# A-fex_PowerShell.net
KiCad netlist of a schematic drawn in EasyEDA Pro
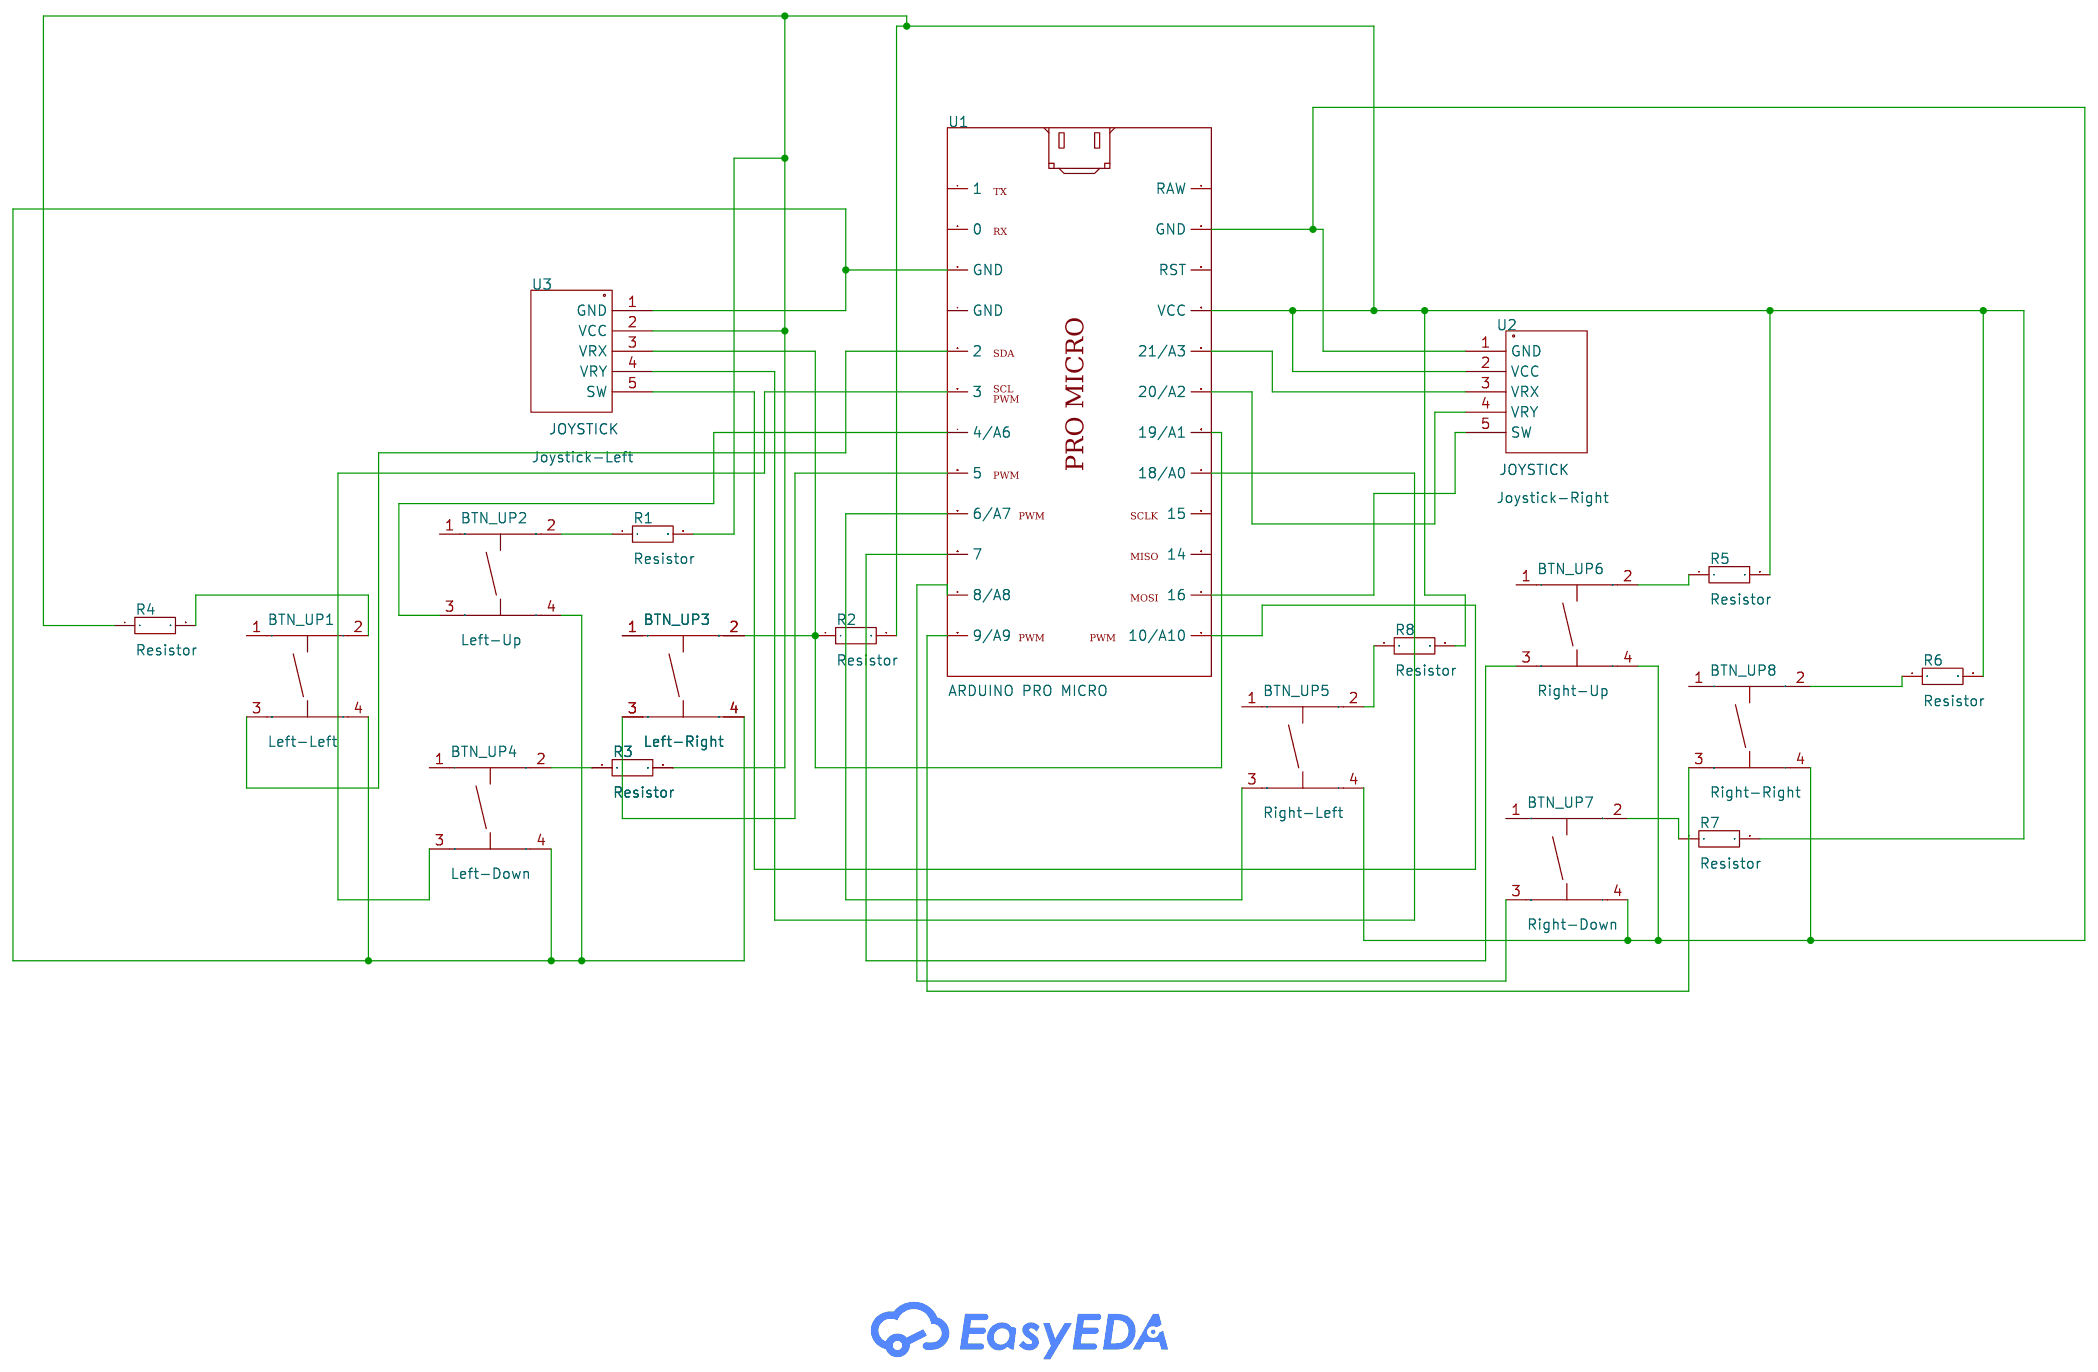
[diagram p0: schematic sheet]

(export (version "E")
  (design (tool "Eeschema 10.0.6"))
  (components
    (comp (ref "BTN_UP1")
      (value "Left-Left")
      (footprint "easyedapro:SW-TH_4P-L12.0-W12.0-P5.00-LS12.5")
      (fields (field (name "Manufacturer") "Boom Precision Elec"))
      (libsource (lib "easyedapro") (part "12X12X7.3 PLAIN TACTILE PUSHBUTTON"))
    )
    (comp (ref "BTN_UP2")
      (value "Left-Up")
      (footprint "easyedapro:SW-TH_4P-L12.0-W12.0-P5.00-LS12.5")
      (fields (field (name "Manufacturer") "Boom Precision Elec"))
      (libsource (lib "easyedapro") (part "12X12X7.3 PLAIN TACTILE PUSHBUTTON"))
    )
    (comp (ref "BTN_UP3")
      (value "Left-Right")
      (footprint "easyedapro:SW-TH_4P-L12.0-W12.0-P5.00-LS12.5")
      (fields (field (name "Manufacturer") "Boom Precision Elec"))
      (libsource (lib "easyedapro") (part "12X12X7.3 PLAIN TACTILE PUSHBUTTON"))
    )
    (comp (ref "BTN_UP4")
      (value "Left-Down")
      (footprint "easyedapro:SW-TH_4P-L12.0-W12.0-P5.00-LS12.5")
      (fields (field (name "Manufacturer") "Boom Precision Elec"))
      (libsource (lib "easyedapro") (part "12X12X7.3 PLAIN TACTILE PUSHBUTTON"))
    )
    (comp (ref "BTN_UP5")
      (value "Right-Left")
      (footprint "easyedapro:SW-TH_4P-L12.0-W12.0-P5.00-LS12.5")
      (fields (field (name "Manufacturer") "Boom Precision Elec"))
      (libsource (lib "easyedapro") (part "12X12X7.3 PLAIN TACTILE PUSHBUTTON"))
    )
    (comp (ref "BTN_UP6")
      (value "Right-Up")
      (footprint "easyedapro:SW-TH_4P-L12.0-W12.0-P5.00-LS12.5")
      (fields (field (name "Manufacturer") "Boom Precision Elec"))
      (libsource (lib "easyedapro") (part "12X12X7.3 PLAIN TACTILE PUSHBUTTON"))
    )
    (comp (ref "BTN_UP7")
      (value "Right-Down")
      (footprint "easyedapro:SW-TH_4P-L12.0-W12.0-P5.00-LS12.5")
      (fields (field (name "Manufacturer") "Boom Precision Elec"))
      (libsource (lib "easyedapro") (part "12X12X7.3 PLAIN TACTILE PUSHBUTTON"))
    )
    (comp (ref "BTN_UP8")
      (value "Right-Right")
      (footprint "easyedapro:SW-TH_4P-L12.0-W12.0-P5.00-LS12.5")
      (fields (field (name "Manufacturer") "Boom Precision Elec"))
      (libsource (lib "easyedapro") (part "12X12X7.3 PLAIN TACTILE PUSHBUTTON"))
    )
    (comp (ref "R1")
      (value "Resistor")
      (footprint "easyedapro:Resistor 1/8w 7mm metal film")
      (fields
        (field (name "Manufacturer Part") "1206W4F1002T5E")
        (field (name "Manufacturer") "UNI-ROYAL(Uniroyal Elec)")
      )
      (libsource (lib "easyedapro") (part "resistor"))
    )
    (comp (ref "R2")
      (value "Resistor")
      (footprint "easyedapro:Resistor 1/8w 7mm metal film")
      (fields
        (field (name "Manufacturer Part") "1206W4F1002T5E")
        (field (name "Manufacturer") "UNI-ROYAL(Uniroyal Elec)")
      )
      (libsource (lib "easyedapro") (part "resistor"))
    )
    (comp (ref "R3")
      (value "Resistor")
      (footprint "easyedapro:Resistor 1/8w 7mm metal film")
      (fields
        (field (name "Manufacturer Part") "1206W4F1002T5E")
        (field (name "Manufacturer") "UNI-ROYAL(Uniroyal Elec)")
      )
      (libsource (lib "easyedapro") (part "resistor"))
    )
    (comp (ref "R4")
      (value "Resistor")
      (footprint "easyedapro:Resistor 1/8w 7mm metal film")
      (fields
        (field (name "Manufacturer Part") "1206W4F1002T5E")
        (field (name "Manufacturer") "UNI-ROYAL(Uniroyal Elec)")
      )
      (libsource (lib "easyedapro") (part "resistor"))
    )
    (comp (ref "R5")
      (value "Resistor")
      (footprint "easyedapro:Resistor 1/8w 7mm metal film")
      (fields
        (field (name "Manufacturer Part") "1206W4F1002T5E")
        (field (name "Manufacturer") "UNI-ROYAL(Uniroyal Elec)")
      )
      (libsource (lib "easyedapro") (part "resistor"))
    )
    (comp (ref "R6")
      (value "Resistor")
      (footprint "easyedapro:Resistor 1/8w 7mm metal film")
      (fields
        (field (name "Manufacturer Part") "1206W4F1002T5E")
        (field (name "Manufacturer") "UNI-ROYAL(Uniroyal Elec)")
      )
      (libsource (lib "easyedapro") (part "resistor"))
    )
    (comp (ref "R7")
      (value "Resistor")
      (footprint "easyedapro:Resistor 1/8w 7mm metal film")
      (fields
        (field (name "Manufacturer Part") "1206W4F1002T5E")
        (field (name "Manufacturer") "UNI-ROYAL(Uniroyal Elec)")
      )
      (libsource (lib "easyedapro") (part "resistor"))
    )
    (comp (ref "R8")
      (value "Resistor")
      (footprint "easyedapro:Resistor 1/8w 7mm metal film")
      (fields
        (field (name "Manufacturer Part") "1206W4F1002T5E")
        (field (name "Manufacturer") "UNI-ROYAL(Uniroyal Elec)")
      )
      (libsource (lib "easyedapro") (part "resistor"))
    )
    (comp (ref "U1")
      (value "ARDUINO PRO MICRO")
      (footprint "easyedapro:ARDUINO MICRO PRO")
      (description "Arduino Pro Micro ATMEGA32U4")
      (fields (field (name "Manufacturer Part") "Arduino Micro Pro"))
      (libsource (lib "easyedapro") (part "ARDUINO PRO MICRO"))
    )
    (comp (ref "U2")
      (value "Joystick-Right")
      (footprint "easyedapro:JOYSTICK")
      (libsource (lib "easyedapro") (part "JOYSTICK"))
    )
    (comp (ref "U3")
      (value "Joystick-Left")
      (footprint "easyedapro:JOYSTICK")
      (libsource (lib "easyedapro") (part "JOYSTICK"))
    )
  )
  (nets
    (net (code "1") (name "Net-(BTN_UP1-Pad2)") (class "Default")
      (node (ref "BTN_UP1") (pin "2") (pinfunction "2_2") (pintype "unspecified"))
      (node (ref "R4") (pin "2") (pinfunction "2_2") (pintype "input"))
    )
    (net (code "2") (name "Net-(BTN_UP2-Pad2)") (class "Default")
      (node (ref "BTN_UP2") (pin "2") (pinfunction "2_2") (pintype "unspecified"))
      (node (ref "R1") (pin "1") (pinfunction "1_1") (pintype "input"))
    )
    (net (code "3") (name "Net-(BTN_UP4-Pad2)") (class "Default")
      (node (ref "BTN_UP4") (pin "2") (pinfunction "2_2") (pintype "unspecified"))
      (node (ref "R3") (pin "1") (pinfunction "1_1") (pintype "input"))
    )
    (net (code "4") (name "Net-(BTN_UP5-Pad2)") (class "Default")
      (node (ref "BTN_UP5") (pin "2") (pinfunction "2_2") (pintype "unspecified"))
      (node (ref "R8") (pin "1") (pinfunction "1_1") (pintype "input"))
    )
    (net (code "5") (name "Net-(BTN_UP6-Pad2)") (class "Default")
      (node (ref "BTN_UP6") (pin "2") (pinfunction "2_2") (pintype "unspecified"))
      (node (ref "R5") (pin "1") (pinfunction "1_1") (pintype "input"))
    )
    (net (code "6") (name "Net-(BTN_UP7-Pad2)") (class "Default")
      (node (ref "BTN_UP7") (pin "2") (pinfunction "2_2") (pintype "unspecified"))
      (node (ref "R7") (pin "1") (pinfunction "1_1") (pintype "input"))
    )
    (net (code "7") (name "Net-(BTN_UP8-Pad2)") (class "Default")
      (node (ref "BTN_UP8") (pin "2") (pinfunction "2_2") (pintype "unspecified"))
      (node (ref "R6") (pin "1") (pinfunction "1_1") (pintype "input"))
    )
    (net (code "8") (name "Net-(U1-2)") (class "Default")
      (node (ref "BTN_UP1") (pin "3") (pinfunction "3_3") (pintype "unspecified"))
      (node (ref "U1") (pin "5") (pinfunction "2_5") (pintype "input"))
    )
    (net (code "9") (name "Net-(U1-3)") (class "Default")
      (node (ref "BTN_UP4") (pin "3") (pinfunction "3_3") (pintype "unspecified"))
      (node (ref "U1") (pin "6") (pinfunction "3_6") (pintype "input"))
    )
    (net (code "10") (name "Net-(U1-4{slash}A6)") (class "Default")
      (node (ref "BTN_UP2") (pin "3") (pinfunction "3_3") (pintype "unspecified"))
      (node (ref "U1") (pin "7") (pinfunction "4/A6_7") (pintype "input"))
    )
    (net (code "11") (name "Net-(U1-5)") (class "Default")
      (node (ref "BTN_UP3") (pin "3") (pinfunction "3_3") (pintype "unspecified"))
      (node (ref "U1") (pin "8") (pinfunction "5_8") (pintype "input"))
    )
    (net (code "12") (name "Net-(U1-6{slash}A7)") (class "Default")
      (node (ref "BTN_UP5") (pin "3") (pinfunction "3_3") (pintype "unspecified"))
      (node (ref "U1") (pin "9") (pinfunction "6/A7_9") (pintype "input"))
    )
    (net (code "13") (name "Net-(U1-7)") (class "Default")
      (node (ref "BTN_UP6") (pin "3") (pinfunction "3_3") (pintype "unspecified"))
      (node (ref "U1") (pin "10") (pinfunction "7_10") (pintype "input"))
    )
    (net (code "14") (name "Net-(U1-8{slash}A8)") (class "Default")
      (node (ref "BTN_UP7") (pin "3") (pinfunction "3_3") (pintype "unspecified"))
      (node (ref "U1") (pin "11") (pinfunction "8/A8_11") (pintype "input"))
    )
    (net (code "15") (name "Net-(U1-9{slash}A9)") (class "Default")
      (node (ref "BTN_UP8") (pin "3") (pinfunction "3_3") (pintype "unspecified"))
      (node (ref "U1") (pin "12") (pinfunction "9/A9_12") (pintype "input"))
    )
    (net (code "16") (name "Net-(U1-10{slash}A10)") (class "Default")
      (node (ref "U1") (pin "13") (pinfunction "10/A10_13") (pintype "input"))
      (node (ref "U3") (pin "5") (pinfunction "SW_5") (pintype "input"))
    )
    (net (code "17") (name "Net-(U1-16)") (class "Default")
      (node (ref "U1") (pin "14") (pinfunction "16_14") (pintype "input"))
      (node (ref "U2") (pin "5") (pinfunction "SW_5") (pintype "input"))
    )
    (net (code "18") (name "Net-(U1-18{slash}A0)") (class "Default")
      (node (ref "U1") (pin "17") (pinfunction "18/A0_17") (pintype "input"))
      (node (ref "U3") (pin "4") (pinfunction "VRY_4") (pintype "input"))
    )
    (net (code "19") (name "Net-(U1-19{slash}A1)") (class "Default")
      (node (ref "BTN_UP3") (pin "2") (pinfunction "2_2") (pintype "unspecified"))
      (node (ref "R2") (pin "1") (pinfunction "1_1") (pintype "input"))
      (node (ref "U1") (pin "18") (pinfunction "19/A1_18") (pintype "input"))
      (node (ref "U3") (pin "3") (pinfunction "VRX_3") (pintype "input"))
    )
    (net (code "20") (name "Net-(U1-20{slash}A2)") (class "Default")
      (node (ref "U1") (pin "19") (pinfunction "20/A2_19") (pintype "input"))
      (node (ref "U2") (pin "4") (pinfunction "VRY_4") (pintype "input"))
    )
    (net (code "21") (name "Net-(U1-21{slash}A3)") (class "Default")
      (node (ref "U1") (pin "20") (pinfunction "21/A3_20") (pintype "input"))
      (node (ref "U2") (pin "3") (pinfunction "VRX_3") (pintype "input"))
    )
    (net (code "22") (name "Net-(U1-VCC)") (class "Default")
      (node (ref "R1") (pin "2") (pinfunction "2_2") (pintype "input"))
      (node (ref "R2") (pin "2") (pinfunction "2_2") (pintype "input"))
      (node (ref "R3") (pin "2") (pinfunction "2_2") (pintype "input"))
      (node (ref "R4") (pin "1") (pinfunction "1_1") (pintype "input"))
      (node (ref "R5") (pin "2") (pinfunction "2_2") (pintype "input"))
      (node (ref "R6") (pin "2") (pinfunction "2_2") (pintype "input"))
      (node (ref "R7") (pin "2") (pinfunction "2_2") (pintype "input"))
      (node (ref "R8") (pin "2") (pinfunction "2_2") (pintype "input"))
      (node (ref "U1") (pin "21") (pinfunction "VCC_21") (pintype "input"))
      (node (ref "U2") (pin "2") (pinfunction "VCC_2") (pintype "input"))
      (node (ref "U3") (pin "2") (pinfunction "VCC_2") (pintype "input"))
    )
    (net (code "23") (name "Net-(U2-GND)") (class "Default")
      (node (ref "BTN_UP5") (pin "4") (pinfunction "4_4") (pintype "unspecified"))
      (node (ref "BTN_UP6") (pin "4") (pinfunction "4_4") (pintype "unspecified"))
      (node (ref "BTN_UP7") (pin "4") (pinfunction "4_4") (pintype "unspecified"))
      (node (ref "BTN_UP8") (pin "4") (pinfunction "4_4") (pintype "unspecified"))
      (node (ref "U1") (pin "23") (pinfunction "GND_23") (pintype "input"))
      (node (ref "U2") (pin "1") (pinfunction "GND_1") (pintype "input"))
    )
    (net (code "24") (name "Net-(U3-GND)") (class "Default")
      (node (ref "BTN_UP1") (pin "4") (pinfunction "4_4") (pintype "unspecified"))
      (node (ref "BTN_UP2") (pin "4") (pinfunction "4_4") (pintype "unspecified"))
      (node (ref "BTN_UP3") (pin "4") (pinfunction "4_4") (pintype "unspecified"))
      (node (ref "BTN_UP4") (pin "4") (pinfunction "4_4") (pintype "unspecified"))
      (node (ref "U1") (pin "3") (pinfunction "GND_3") (pintype "input"))
      (node (ref "U3") (pin "1") (pinfunction "GND_1") (pintype "input"))
    )
    (net (code "25") (name "unconnected-(BTN_UP1-Pad1)") (class "Default")
      (node (ref "BTN_UP1") (pin "1") (pinfunction "1_1") (pintype "unspecified"))
    )
    (net (code "26") (name "unconnected-(BTN_UP2-Pad1)") (class "Default")
      (node (ref "BTN_UP2") (pin "1") (pinfunction "1_1") (pintype "unspecified"))
    )
    (net (code "27") (name "unconnected-(BTN_UP3-Pad1)") (class "Default")
      (node (ref "BTN_UP3") (pin "1") (pinfunction "1_1") (pintype "unspecified"))
    )
    (net (code "28") (name "unconnected-(BTN_UP4-Pad1)") (class "Default")
      (node (ref "BTN_UP4") (pin "1") (pinfunction "1_1") (pintype "unspecified"))
    )
    (net (code "29") (name "unconnected-(BTN_UP5-Pad1)") (class "Default")
      (node (ref "BTN_UP5") (pin "1") (pinfunction "1_1") (pintype "unspecified"))
    )
    (net (code "30") (name "unconnected-(BTN_UP6-Pad1)") (class "Default")
      (node (ref "BTN_UP6") (pin "1") (pinfunction "1_1") (pintype "unspecified"))
    )
    (net (code "31") (name "unconnected-(BTN_UP7-Pad1)") (class "Default")
      (node (ref "BTN_UP7") (pin "1") (pinfunction "1_1") (pintype "unspecified"))
    )
    (net (code "32") (name "unconnected-(BTN_UP8-Pad1)") (class "Default")
      (node (ref "BTN_UP8") (pin "1") (pinfunction "1_1") (pintype "unspecified"))
    )
    (net (code "33") (name "unconnected-(U1-0-Pad2)") (class "Default")
      (node (ref "U1") (pin "2") (pinfunction "0_2") (pintype "input"))
    )
    (net (code "34") (name "unconnected-(U1-14-Pad15)") (class "Default")
      (node (ref "U1") (pin "15") (pinfunction "14_15") (pintype "input"))
    )
    (net (code "35") (name "unconnected-(U1-15-Pad16)") (class "Default")
      (node (ref "U1") (pin "16") (pinfunction "15_16") (pintype "input"))
    )
    (net (code "36") (name "unconnected-(U1-GND-Pad4)") (class "Default")
      (node (ref "U1") (pin "4") (pinfunction "GND_4") (pintype "input"))
    )
    (net (code "37") (name "unconnected-(U1-Pad1)") (class "Default")
      (node (ref "U1") (pin "1") (pinfunction "1_1") (pintype "input"))
    )
    (net (code "38") (name "unconnected-(U1-RAW-Pad24)") (class "Default")
      (node (ref "U1") (pin "24") (pinfunction "RAW_24") (pintype "input"))
    )
    (net (code "39") (name "unconnected-(U1-RST-Pad22)") (class "Default")
      (node (ref "U1") (pin "22") (pinfunction "RST_22") (pintype "input"))
    )
  )
)
